# ToolChanger_RevA.net
KiCad netlist of a schematic drawn in EAGLE
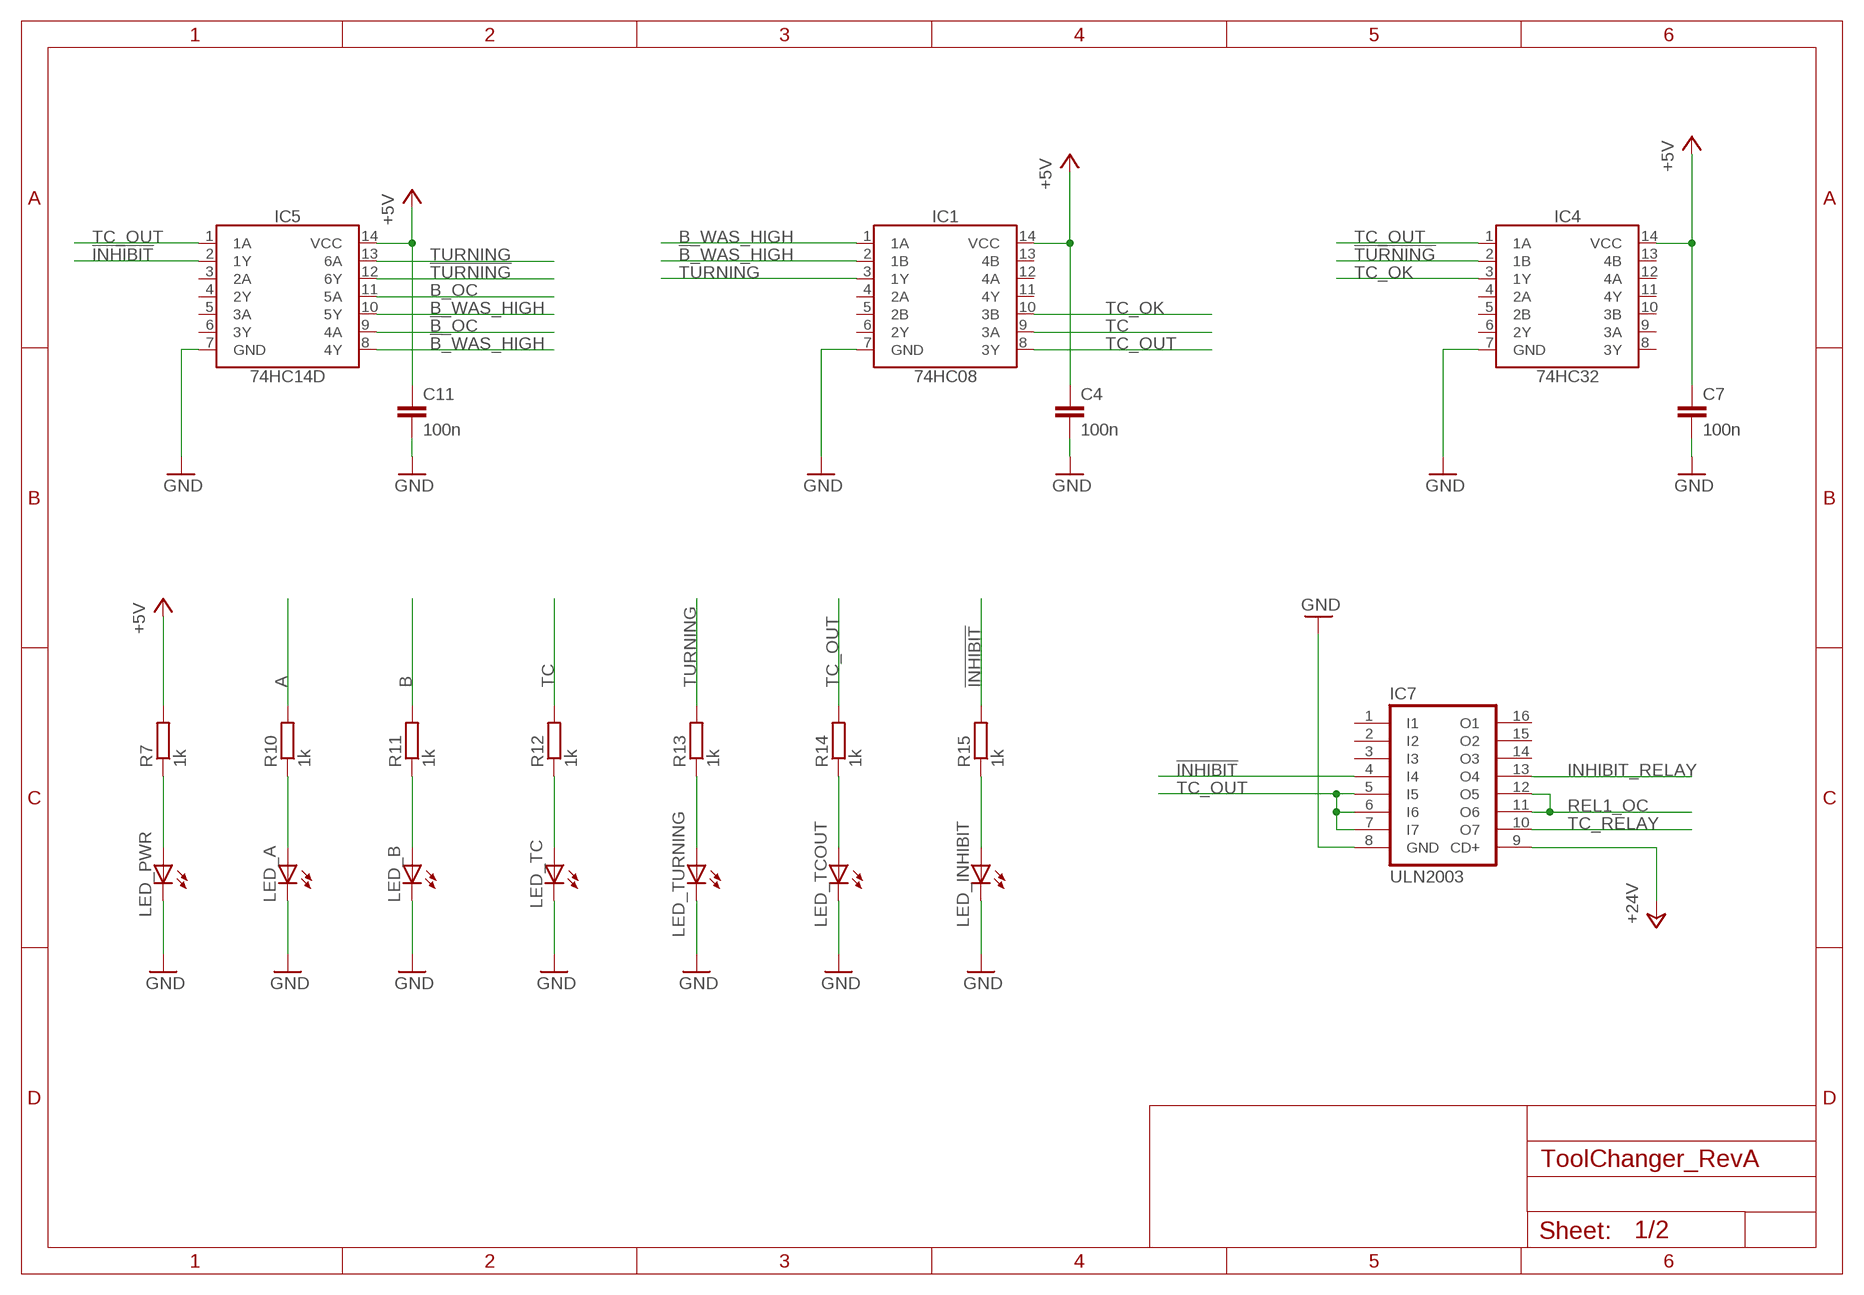
[diagram p0: schematic, sheet 1]
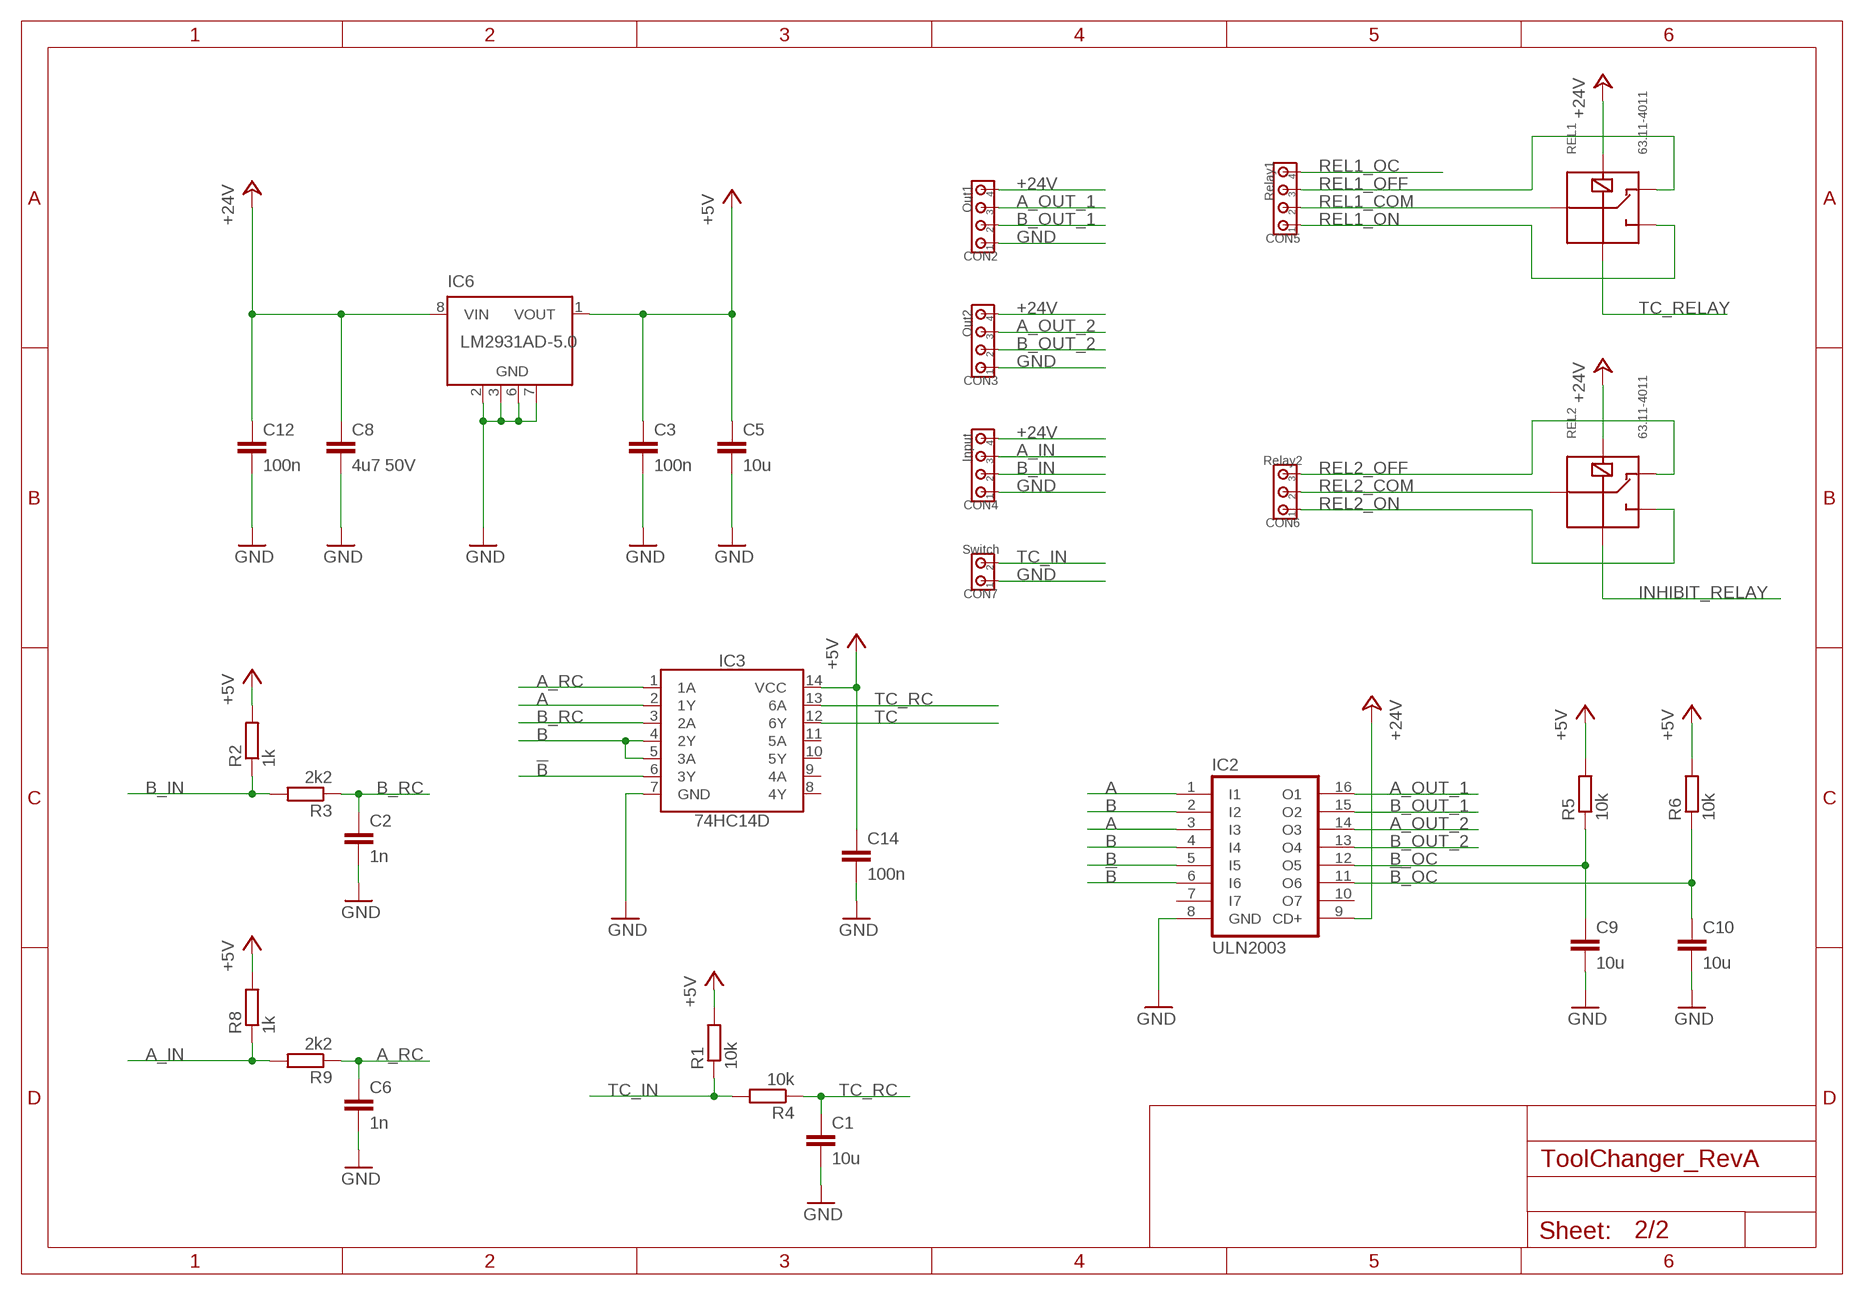
[diagram p1: schematic, sheet 2]

(export (version "E")
  (design (tool "Eeschema 10.0.6"))
  (components
    (comp (ref "C4")
      (value "100n")
      (footprint "eagle-import:C0805")
      (libsource (lib "eagle-import") (part "CC0805"))
    )
    (comp (ref "C7")
      (value "100n")
      (footprint "eagle-import:C0805")
      (libsource (lib "eagle-import") (part "CC0805"))
    )
    (comp (ref "C11")
      (value "100n")
      (footprint "eagle-import:C0805")
      (libsource (lib "eagle-import") (part "CC0805"))
    )
    (comp (ref "IC1")
      (value "74HC08")
      (footprint "eagle-import:SO14")
      (libsource (lib "eagle-import") (part "74HC08"))
    )
    (comp (ref "IC4")
      (value "74HC32")
      (footprint "eagle-import:SO14")
      (libsource (lib "eagle-import") (part "74HC32"))
    )
    (comp (ref "IC5")
      (value "74HC14D")
      (footprint "eagle-import:SO14")
      (libsource (lib "eagle-import") (part "74HC14D"))
    )
    (comp (ref "IC7")
      (value "ULN2003")
      (footprint "eagle-import:SO16")
      (libsource (lib "eagle-import") (part "ULN2003"))
    )
    (comp (ref "LED_A")
      (value "LED0805_NB")
      (footprint "eagle-import:LED0805_NOBOARDER")
      (libsource (lib "eagle-import") (part "LED0805_NB"))
    )
    (comp (ref "LED_B")
      (value "LED0805_NB")
      (footprint "eagle-import:LED0805_NOBOARDER")
      (libsource (lib "eagle-import") (part "LED0805_NB"))
    )
    (comp (ref "LED_INHIBIT")
      (value "LED0805_NB")
      (footprint "eagle-import:LED0805_NOBOARDER")
      (libsource (lib "eagle-import") (part "LED0805_NB"))
    )
    (comp (ref "LED_PWR")
      (value "LED0805_NB")
      (footprint "eagle-import:LED0805_NOBOARDER")
      (libsource (lib "eagle-import") (part "LED0805_NB"))
    )
    (comp (ref "LED_TC")
      (value "LED0805_NB")
      (footprint "eagle-import:LED0805_NOBOARDER")
      (libsource (lib "eagle-import") (part "LED0805_NB"))
    )
    (comp (ref "LED_TCOUT")
      (value "LED0805_NB")
      (footprint "eagle-import:LED0805_NOBOARDER")
      (libsource (lib "eagle-import") (part "LED0805_NB"))
    )
    (comp (ref "LED_TURNING")
      (value "LED0805_NB")
      (footprint "eagle-import:LED0805_NOBOARDER")
      (libsource (lib "eagle-import") (part "LED0805_NB"))
    )
    (comp (ref "R7")
      (value "1k")
      (footprint "eagle-import:R0805")
      (libsource (lib "eagle-import") (part "RESISTORR0805"))
    )
    (comp (ref "R10")
      (value "1k")
      (footprint "eagle-import:R0805")
      (libsource (lib "eagle-import") (part "RESISTORR0805"))
    )
    (comp (ref "R11")
      (value "1k")
      (footprint "eagle-import:R0805")
      (libsource (lib "eagle-import") (part "RESISTORR0805"))
    )
    (comp (ref "R12")
      (value "1k")
      (footprint "eagle-import:R0805")
      (libsource (lib "eagle-import") (part "RESISTORR0805"))
    )
    (comp (ref "R13")
      (value "1k")
      (footprint "eagle-import:R0805")
      (libsource (lib "eagle-import") (part "RESISTORR0805"))
    )
    (comp (ref "R14")
      (value "1k")
      (footprint "eagle-import:R0805")
      (libsource (lib "eagle-import") (part "RESISTORR0805"))
    )
    (comp (ref "R15")
      (value "1k")
      (footprint "eagle-import:R0805")
      (libsource (lib "eagle-import") (part "RESISTORR0805"))
    )
    (comp (ref "C1")
      (value "10u")
      (footprint "eagle-import:C0805")
      (libsource (lib "eagle-import") (part "CC0805"))
    )
    (comp (ref "C2")
      (value "1n")
      (footprint "eagle-import:C0805")
      (libsource (lib "eagle-import") (part "CC0805"))
    )
    (comp (ref "C3")
      (value "100n")
      (footprint "eagle-import:C0805")
      (libsource (lib "eagle-import") (part "CC0805"))
    )
    (comp (ref "C5")
      (value "10u")
      (footprint "eagle-import:C0805")
      (libsource (lib "eagle-import") (part "CC0805"))
    )
    (comp (ref "C6")
      (value "1n")
      (footprint "eagle-import:C0805")
      (libsource (lib "eagle-import") (part "CC0805"))
    )
    (comp (ref "C8")
      (value "4u7 50V")
      (footprint "eagle-import:C1206")
      (libsource (lib "eagle-import") (part "CC1206"))
    )
    (comp (ref "C9")
      (value "10u")
      (footprint "eagle-import:C0805")
      (libsource (lib "eagle-import") (part "CC0805"))
    )
    (comp (ref "C10")
      (value "10u")
      (footprint "eagle-import:C0805")
      (libsource (lib "eagle-import") (part "CC0805"))
    )
    (comp (ref "C12")
      (value "100n")
      (footprint "eagle-import:C0805")
      (libsource (lib "eagle-import") (part "CC0805"))
    )
    (comp (ref "C14")
      (value "100n")
      (footprint "eagle-import:C0805")
      (libsource (lib "eagle-import") (part "CC0805"))
    )
    (comp (ref "CON2")
      (value "Out1")
      (footprint "eagle-import:3.5MM_4X")
      (libsource (lib "eagle-import") (part "CON_4X3.5MM"))
    )
    (comp (ref "CON3")
      (value "Out2")
      (footprint "eagle-import:3.5MM_4X")
      (libsource (lib "eagle-import") (part "CON_4X3.5MM"))
    )
    (comp (ref "CON4")
      (value "Input")
      (footprint "eagle-import:3.5MM_4X")
      (libsource (lib "eagle-import") (part "CON_4X3.5MM"))
    )
    (comp (ref "CON5")
      (value "Relay1")
      (footprint "eagle-import:200MIL_4X")
      (libsource (lib "eagle-import") (part "CON_4X200MIL"))
    )
    (comp (ref "CON6")
      (value "Relay2")
      (footprint "eagle-import:200MIL_3X")
      (libsource (lib "eagle-import") (part "CON_3X200MIL"))
    )
    (comp (ref "CON7")
      (value "Switch")
      (footprint "eagle-import:3.5MM_2X")
      (libsource (lib "eagle-import") (part "CON_2X3.5MM"))
    )
    (comp (ref "IC2")
      (value "ULN2003")
      (footprint "eagle-import:SO16")
      (libsource (lib "eagle-import") (part "ULN2003"))
    )
    (comp (ref "IC3")
      (value "74HC14D")
      (footprint "eagle-import:SO14")
      (libsource (lib "eagle-import") (part "74HC14D"))
    )
    (comp (ref "IC6")
      (value "LM2931AD-5.0")
      (footprint "eagle-import:SOIC8")
      (libsource (lib "eagle-import") (part "LM2931AD-5.0"))
    )
    (comp (ref "R1")
      (value "10k")
      (footprint "eagle-import:R0805")
      (libsource (lib "eagle-import") (part "RESISTORR0805"))
    )
    (comp (ref "R2")
      (value "1k")
      (footprint "eagle-import:R0805")
      (libsource (lib "eagle-import") (part "RESISTORR0805"))
    )
    (comp (ref "R3")
      (value "2k2")
      (footprint "eagle-import:R0805")
      (libsource (lib "eagle-import") (part "RESISTORR0805"))
    )
    (comp (ref "R4")
      (value "10k")
      (footprint "eagle-import:R0805")
      (libsource (lib "eagle-import") (part "RESISTORR0805"))
    )
    (comp (ref "R5")
      (value "10k")
      (footprint "eagle-import:R0805")
      (libsource (lib "eagle-import") (part "RESISTORR0805"))
    )
    (comp (ref "R6")
      (value "10k")
      (footprint "eagle-import:R0805")
      (libsource (lib "eagle-import") (part "RESISTORR0805"))
    )
    (comp (ref "R8")
      (value "1k")
      (footprint "eagle-import:R0805")
      (libsource (lib "eagle-import") (part "RESISTORR0805"))
    )
    (comp (ref "R9")
      (value "2k2")
      (footprint "eagle-import:R0805")
      (libsource (lib "eagle-import") (part "RESISTORR0805"))
    )
    (comp (ref "REL1")
      (value "63.11-4011")
      (footprint "eagle-import:G5LE")
      (libsource (lib "eagle-import") (part "63.11-4011"))
    )
    (comp (ref "REL2")
      (value "63.11-4011")
      (footprint "eagle-import:G5LE")
      (libsource (lib "eagle-import") (part "63.11-4011"))
    )
  )
  (nets
    (net (code "1") (name "+5V") (class "Default")
      (node (ref "C11") (pin "1") (pinfunction "1_1") (pintype "passive"))
      (node (ref "C14") (pin "1") (pinfunction "1_1") (pintype "passive"))
      (node (ref "C3") (pin "1") (pinfunction "1_1") (pintype "passive"))
      (node (ref "C4") (pin "1") (pinfunction "1_1") (pintype "passive"))
      (node (ref "C5") (pin "1") (pinfunction "1_1") (pintype "passive"))
      (node (ref "C7") (pin "1") (pinfunction "1_1") (pintype "passive"))
      (node (ref "IC1") (pin "14") (pinfunction "VCC_14") (pintype "power_in"))
      (node (ref "IC3") (pin "14") (pinfunction "VCC_14") (pintype "power_in"))
      (node (ref "IC4") (pin "14") (pinfunction "VCC_14") (pintype "power_in"))
      (node (ref "IC5") (pin "14") (pinfunction "VCC_14") (pintype "power_in"))
      (node (ref "IC6") (pin "1") (pinfunction "VOUT_1") (pintype "output"))
      (node (ref "R1") (pin "2") (pinfunction "2_2") (pintype "passive"))
      (node (ref "R2") (pin "2") (pinfunction "2_2") (pintype "passive"))
      (node (ref "R5") (pin "2") (pinfunction "2_2") (pintype "passive"))
      (node (ref "R6") (pin "2") (pinfunction "2_2") (pintype "passive"))
      (node (ref "R7") (pin "2") (pinfunction "2_2") (pintype "passive"))
      (node (ref "R8") (pin "2") (pinfunction "2_2") (pintype "passive"))
    )
    (net (code "2") (name "+24V") (class "Default")
      (node (ref "C12") (pin "1") (pinfunction "1_1") (pintype "passive"))
      (node (ref "C8") (pin "1") (pinfunction "1_1") (pintype "passive"))
      (node (ref "CON2") (pin "4") (pinfunction "4_4") (pintype "passive"))
      (node (ref "CON3") (pin "4") (pinfunction "4_4") (pintype "passive"))
      (node (ref "CON4") (pin "4") (pinfunction "4_4") (pintype "passive"))
      (node (ref "IC2") (pin "9") (pinfunction "CD+_9") (pintype "passive"))
      (node (ref "IC6") (pin "8") (pinfunction "VIN_8") (pintype "passive"))
      (node (ref "IC7") (pin "9") (pinfunction "CD+_9") (pintype "passive"))
      (node (ref "REL1") (pin "2") (pinfunction "2_2") (pintype "passive"))
      (node (ref "REL2") (pin "2") (pinfunction "2_2") (pintype "passive"))
    )
    (net (code "3") (name "A") (class "Default")
      (node (ref "IC2") (pin "1") (pinfunction "I1_1") (pintype "input"))
      (node (ref "IC2") (pin "3") (pinfunction "I3_3") (pintype "input"))
      (node (ref "IC3") (pin "2") (pinfunction "1Y_2") (pintype "input"))
      (node (ref "R10") (pin "2") (pinfunction "2_2") (pintype "passive"))
    )
    (net (code "4") (name "A_IN") (class "Default")
      (node (ref "CON4") (pin "3") (pinfunction "3_3") (pintype "passive"))
      (node (ref "R8") (pin "1") (pinfunction "1_1") (pintype "passive"))
      (node (ref "R9") (pin "2") (pinfunction "2_2") (pintype "passive"))
    )
    (net (code "5") (name "A_OUT_1") (class "Default")
      (node (ref "CON2") (pin "3") (pinfunction "3_3") (pintype "passive"))
      (node (ref "IC2") (pin "16") (pinfunction "O1_16") (pintype "open_collector"))
    )
    (net (code "6") (name "A_OUT_2") (class "Default")
      (node (ref "CON3") (pin "3") (pinfunction "3_3") (pintype "passive"))
      (node (ref "IC2") (pin "14") (pinfunction "O3_14") (pintype "open_collector"))
    )
    (net (code "7") (name "A_RC") (class "Default")
      (node (ref "C6") (pin "1") (pinfunction "1_1") (pintype "passive"))
      (node (ref "IC3") (pin "1") (pinfunction "1A_1") (pintype "input"))
      (node (ref "R9") (pin "1") (pinfunction "1_1") (pintype "passive"))
    )
    (net (code "8") (name "B") (class "Default")
      (node (ref "IC2") (pin "2") (pinfunction "I2_2") (pintype "input"))
      (node (ref "IC2") (pin "4") (pinfunction "I4_4") (pintype "input"))
      (node (ref "IC2") (pin "5") (pinfunction "I5_5") (pintype "input"))
      (node (ref "IC3") (pin "4") (pinfunction "2Y_4") (pintype "input"))
      (node (ref "IC3") (pin "5") (pinfunction "3A_5") (pintype "input"))
      (node (ref "R11") (pin "2") (pinfunction "2_2") (pintype "passive"))
    )
    (net (code "9") (name "B_IN") (class "Default")
      (node (ref "CON4") (pin "2") (pinfunction "2_2") (pintype "passive"))
      (node (ref "R2") (pin "1") (pinfunction "1_1") (pintype "passive"))
      (node (ref "R3") (pin "2") (pinfunction "2_2") (pintype "passive"))
    )
    (net (code "10") (name "B_OC") (class "Default")
      (node (ref "C9") (pin "1") (pinfunction "1_1") (pintype "passive"))
      (node (ref "IC2") (pin "12") (pinfunction "O5_12") (pintype "open_collector"))
      (node (ref "IC5") (pin "11") (pinfunction "5A_11") (pintype "bidirectional"))
      (node (ref "R5") (pin "1") (pinfunction "1_1") (pintype "passive"))
    )
    (net (code "11") (name "B_OUT_1") (class "Default")
      (node (ref "CON2") (pin "2") (pinfunction "2_2") (pintype "passive"))
      (node (ref "IC2") (pin "15") (pinfunction "O2_15") (pintype "open_collector"))
    )
    (net (code "12") (name "B_OUT_2") (class "Default")
      (node (ref "CON3") (pin "2") (pinfunction "2_2") (pintype "passive"))
      (node (ref "IC2") (pin "13") (pinfunction "O4_13") (pintype "open_collector"))
    )
    (net (code "13") (name "B_RC") (class "Default")
      (node (ref "C2") (pin "1") (pinfunction "1_1") (pintype "passive"))
      (node (ref "IC3") (pin "3") (pinfunction "2A_3") (pintype "input"))
      (node (ref "R3") (pin "1") (pinfunction "1_1") (pintype "passive"))
    )
    (net (code "14") (name "B_WAS_HIGH") (class "Default")
      (node (ref "IC1") (pin "1") (pinfunction "1A_1") (pintype "input"))
      (node (ref "IC5") (pin "10") (pinfunction "5Y_10") (pintype "bidirectional"))
    )
    (net (code "15") (name "GND") (class "Default")
      (node (ref "C1") (pin "2") (pinfunction "2_2") (pintype "passive"))
      (node (ref "C10") (pin "2") (pinfunction "2_2") (pintype "passive"))
      (node (ref "C11") (pin "2") (pinfunction "2_2") (pintype "passive"))
      (node (ref "C12") (pin "2") (pinfunction "2_2") (pintype "passive"))
      (node (ref "C14") (pin "2") (pinfunction "2_2") (pintype "passive"))
      (node (ref "C2") (pin "2") (pinfunction "2_2") (pintype "passive"))
      (node (ref "C3") (pin "2") (pinfunction "2_2") (pintype "passive"))
      (node (ref "C4") (pin "2") (pinfunction "2_2") (pintype "passive"))
      (node (ref "C5") (pin "2") (pinfunction "2_2") (pintype "passive"))
      (node (ref "C6") (pin "2") (pinfunction "2_2") (pintype "passive"))
      (node (ref "C7") (pin "2") (pinfunction "2_2") (pintype "passive"))
      (node (ref "C8") (pin "2") (pinfunction "2_2") (pintype "passive"))
      (node (ref "C9") (pin "2") (pinfunction "2_2") (pintype "passive"))
      (node (ref "CON2") (pin "1") (pinfunction "1_1") (pintype "passive"))
      (node (ref "CON3") (pin "1") (pinfunction "1_1") (pintype "passive"))
      (node (ref "CON4") (pin "1") (pinfunction "1_1") (pintype "passive"))
      (node (ref "CON7") (pin "1") (pinfunction "1_1") (pintype "passive"))
      (node (ref "IC1") (pin "7") (pinfunction "GND_7") (pintype "bidirectional"))
      (node (ref "IC2") (pin "8") (pinfunction "GND_8") (pintype "power_in"))
      (node (ref "IC3") (pin "7") (pinfunction "GND_7") (pintype "bidirectional"))
      (node (ref "IC4") (pin "7") (pinfunction "GND_7") (pintype "bidirectional"))
      (node (ref "IC5") (pin "7") (pinfunction "GND_7") (pintype "bidirectional"))
      (node (ref "IC6") (pin "2") (pinfunction "GND_2") (pintype "power_in"))
      (node (ref "IC6") (pin "3") (pinfunction "GND_3") (pintype "power_in"))
      (node (ref "IC6") (pin "6") (pinfunction "GND_6") (pintype "power_in"))
      (node (ref "IC6") (pin "7") (pinfunction "GND_7") (pintype "power_in"))
      (node (ref "IC7") (pin "8") (pinfunction "GND_8") (pintype "power_in"))
      (node (ref "LED_A") (pin "C") (pinfunction "C_C") (pintype "passive"))
      (node (ref "LED_B") (pin "C") (pinfunction "C_C") (pintype "passive"))
      (node (ref "LED_INHIBIT") (pin "C") (pinfunction "C_C") (pintype "passive"))
      (node (ref "LED_PWR") (pin "C") (pinfunction "C_C") (pintype "passive"))
      (node (ref "LED_TC") (pin "C") (pinfunction "C_C") (pintype "passive"))
      (node (ref "LED_TCOUT") (pin "C") (pinfunction "C_C") (pintype "passive"))
      (node (ref "LED_TURNING") (pin "C") (pinfunction "C_C") (pintype "passive"))
    )
    (net (code "16") (name "INHIBIT_RELAY") (class "Default")
      (node (ref "IC7") (pin "13") (pinfunction "O4_13") (pintype "open_collector"))
      (node (ref "REL2") (pin "1") (pinfunction "1_1") (pintype "passive"))
    )
    (net (code "17") (name "Net-(LED_A-PadA)") (class "Default")
      (node (ref "LED_A") (pin "A") (pinfunction "A_A") (pintype "passive"))
      (node (ref "R10") (pin "1") (pinfunction "1_1") (pintype "passive"))
    )
    (net (code "18") (name "Net-(LED_B-PadA)") (class "Default")
      (node (ref "LED_B") (pin "A") (pinfunction "A_A") (pintype "passive"))
      (node (ref "R11") (pin "1") (pinfunction "1_1") (pintype "passive"))
    )
    (net (code "19") (name "Net-(LED_INHIBIT-PadA)") (class "Default")
      (node (ref "LED_INHIBIT") (pin "A") (pinfunction "A_A") (pintype "passive"))
      (node (ref "R15") (pin "1") (pinfunction "1_1") (pintype "passive"))
    )
    (net (code "20") (name "Net-(LED_PWR-PadA)") (class "Default")
      (node (ref "LED_PWR") (pin "A") (pinfunction "A_A") (pintype "passive"))
      (node (ref "R7") (pin "1") (pinfunction "1_1") (pintype "passive"))
    )
    (net (code "21") (name "Net-(LED_TC-PadA)") (class "Default")
      (node (ref "LED_TC") (pin "A") (pinfunction "A_A") (pintype "passive"))
      (node (ref "R12") (pin "1") (pinfunction "1_1") (pintype "passive"))
    )
    (net (code "22") (name "Net-(LED_TCOUT-PadA)") (class "Default")
      (node (ref "LED_TCOUT") (pin "A") (pinfunction "A_A") (pintype "passive"))
      (node (ref "R14") (pin "1") (pinfunction "1_1") (pintype "passive"))
    )
    (net (code "23") (name "Net-(LED_TURNING-PadA)") (class "Default")
      (node (ref "LED_TURNING") (pin "A") (pinfunction "A_A") (pintype "passive"))
      (node (ref "R13") (pin "1") (pinfunction "1_1") (pintype "passive"))
    )
    (net (code "24") (name "REL1_COM") (class "Default")
      (node (ref "CON5") (pin "2") (pinfunction "2_2") (pintype "passive"))
      (node (ref "REL1") (pin "COM") (pinfunction "COM_COM") (pintype "passive"))
    )
    (net (code "25") (name "REL1_OC") (class "Default")
      (node (ref "CON5") (pin "4") (pinfunction "4_4") (pintype "passive"))
      (node (ref "IC7") (pin "11") (pinfunction "O6_11") (pintype "open_collector"))
      (node (ref "IC7") (pin "12") (pinfunction "O5_12") (pintype "open_collector"))
    )
    (net (code "26") (name "REL1_OFF") (class "Default")
      (node (ref "CON5") (pin "3") (pinfunction "3_3") (pintype "passive"))
      (node (ref "REL1") (pin "O") (pinfunction "O_O") (pintype "passive"))
    )
    (net (code "27") (name "REL1_ON") (class "Default")
      (node (ref "CON5") (pin "1") (pinfunction "1_1") (pintype "passive"))
      (node (ref "REL1") (pin "C") (pinfunction "C_C") (pintype "passive"))
    )
    (net (code "28") (name "REL2_COM") (class "Default")
      (node (ref "CON6") (pin "2") (pinfunction "2_2") (pintype "passive"))
      (node (ref "REL2") (pin "COM") (pinfunction "COM_COM") (pintype "passive"))
    )
    (net (code "29") (name "REL2_OFF") (class "Default")
      (node (ref "CON6") (pin "3") (pinfunction "3_3") (pintype "passive"))
      (node (ref "REL2") (pin "O") (pinfunction "O_O") (pintype "passive"))
    )
    (net (code "30") (name "REL2_ON") (class "Default")
      (node (ref "CON6") (pin "1") (pinfunction "1_1") (pintype "passive"))
      (node (ref "REL2") (pin "C") (pinfunction "C_C") (pintype "passive"))
    )
    (net (code "31") (name "TC") (class "Default")
      (node (ref "IC1") (pin "9") (pinfunction "3A_9") (pintype "bidirectional"))
      (node (ref "IC3") (pin "12") (pinfunction "6Y_12") (pintype "bidirectional"))
      (node (ref "R12") (pin "2") (pinfunction "2_2") (pintype "passive"))
    )
    (net (code "32") (name "TC_IN") (class "Default")
      (node (ref "CON7") (pin "2") (pinfunction "2_2") (pintype "passive"))
      (node (ref "R1") (pin "1") (pinfunction "1_1") (pintype "passive"))
      (node (ref "R4") (pin "2") (pinfunction "2_2") (pintype "passive"))
    )
    (net (code "33") (name "TC_OK") (class "Default")
      (node (ref "IC1") (pin "10") (pinfunction "3B_10") (pintype "bidirectional"))
      (node (ref "IC4") (pin "3") (pinfunction "1Y_3") (pintype "input"))
    )
    (net (code "34") (name "TC_OUT") (class "Default")
      (node (ref "IC1") (pin "8") (pinfunction "3Y_8") (pintype "bidirectional"))
      (node (ref "IC4") (pin "1") (pinfunction "1A_1") (pintype "input"))
      (node (ref "IC5") (pin "1") (pinfunction "1A_1") (pintype "input"))
      (node (ref "IC7") (pin "5") (pinfunction "I5_5") (pintype "input"))
      (node (ref "IC7") (pin "6") (pinfunction "I6_6") (pintype "input"))
      (node (ref "IC7") (pin "7") (pinfunction "I7_7") (pintype "input"))
      (node (ref "R14") (pin "2") (pinfunction "2_2") (pintype "passive"))
    )
    (net (code "35") (name "TC_RC") (class "Default")
      (node (ref "C1") (pin "1") (pinfunction "1_1") (pintype "passive"))
      (node (ref "IC3") (pin "13") (pinfunction "6A_13") (pintype "bidirectional"))
      (node (ref "R4") (pin "1") (pinfunction "1_1") (pintype "passive"))
    )
    (net (code "36") (name "TC_RELAY") (class "Default")
      (node (ref "IC7") (pin "10") (pinfunction "O7_10") (pintype "open_collector"))
      (node (ref "REL1") (pin "1") (pinfunction "1_1") (pintype "passive"))
    )
    (net (code "37") (name "TURNING") (class "Default")
      (node (ref "IC1") (pin "3") (pinfunction "1Y_3") (pintype "input"))
      (node (ref "IC5") (pin "13") (pinfunction "6A_13") (pintype "bidirectional"))
      (node (ref "R13") (pin "2") (pinfunction "2_2") (pintype "passive"))
    )
    (net (code "38") (name "unconnected-(IC1-2A-Pad4)") (class "Default")
      (node (ref "IC1") (pin "4") (pinfunction "2A_4") (pintype "input"))
    )
    (net (code "39") (name "unconnected-(IC1-2B-Pad5)") (class "Default")
      (node (ref "IC1") (pin "5") (pinfunction "2B_5") (pintype "input"))
    )
    (net (code "40") (name "unconnected-(IC1-2Y-Pad6)") (class "Default")
      (node (ref "IC1") (pin "6") (pinfunction "2Y_6") (pintype "input"))
    )
    (net (code "41") (name "unconnected-(IC1-4A-Pad12)") (class "Default")
      (node (ref "IC1") (pin "12") (pinfunction "4A_12") (pintype "bidirectional"))
    )
    (net (code "42") (name "unconnected-(IC1-4B-Pad13)") (class "Default")
      (node (ref "IC1") (pin "13") (pinfunction "4B_13") (pintype "bidirectional"))
    )
    (net (code "43") (name "unconnected-(IC1-4Y-Pad11)") (class "Default")
      (node (ref "IC1") (pin "11") (pinfunction "4Y_11") (pintype "bidirectional"))
    )
    (net (code "44") (name "unconnected-(IC2-I7-Pad7)") (class "Default")
      (node (ref "IC2") (pin "7") (pinfunction "I7_7") (pintype "input"))
    )
    (net (code "45") (name "unconnected-(IC2-O7-Pad10)") (class "Default")
      (node (ref "IC2") (pin "10") (pinfunction "O7_10") (pintype "open_collector"))
    )
    (net (code "46") (name "unconnected-(IC3-4A-Pad9)") (class "Default")
      (node (ref "IC3") (pin "9") (pinfunction "4A_9") (pintype "bidirectional"))
    )
    (net (code "47") (name "unconnected-(IC3-4Y-Pad8)") (class "Default")
      (node (ref "IC3") (pin "8") (pinfunction "4Y_8") (pintype "bidirectional"))
    )
    (net (code "48") (name "unconnected-(IC3-5A-Pad11)") (class "Default")
      (node (ref "IC3") (pin "11") (pinfunction "5A_11") (pintype "bidirectional"))
    )
    (net (code "49") (name "unconnected-(IC3-5Y-Pad10)") (class "Default")
      (node (ref "IC3") (pin "10") (pinfunction "5Y_10") (pintype "bidirectional"))
    )
    (net (code "50") (name "unconnected-(IC4-2A-Pad4)") (class "Default")
      (node (ref "IC4") (pin "4") (pinfunction "2A_4") (pintype "input"))
    )
    (net (code "51") (name "unconnected-(IC4-2B-Pad5)") (class "Default")
      (node (ref "IC4") (pin "5") (pinfunction "2B_5") (pintype "input"))
    )
    (net (code "52") (name "unconnected-(IC4-2Y-Pad6)") (class "Default")
      (node (ref "IC4") (pin "6") (pinfunction "2Y_6") (pintype "input"))
    )
    (net (code "53") (name "unconnected-(IC4-3A-Pad9)") (class "Default")
      (node (ref "IC4") (pin "9") (pinfunction "3A_9") (pintype "bidirectional"))
    )
    (net (code "54") (name "unconnected-(IC4-3B-Pad10)") (class "Default")
      (node (ref "IC4") (pin "10") (pinfunction "3B_10") (pintype "bidirectional"))
    )
    (net (code "55") (name "unconnected-(IC4-3Y-Pad8)") (class "Default")
      (node (ref "IC4") (pin "8") (pinfunction "3Y_8") (pintype "bidirectional"))
    )
    (net (code "56") (name "unconnected-(IC4-4A-Pad12)") (class "Default")
      (node (ref "IC4") (pin "12") (pinfunction "4A_12") (pintype "bidirectional"))
    )
    (net (code "57") (name "unconnected-(IC4-4B-Pad13)") (class "Default")
      (node (ref "IC4") (pin "13") (pinfunction "4B_13") (pintype "bidirectional"))
    )
    (net (code "58") (name "unconnected-(IC4-4Y-Pad11)") (class "Default")
      (node (ref "IC4") (pin "11") (pinfunction "4Y_11") (pintype "bidirectional"))
    )
    (net (code "59") (name "unconnected-(IC5-2A-Pad3)") (class "Default")
      (node (ref "IC5") (pin "3") (pinfunction "2A_3") (pintype "input"))
    )
    (net (code "60") (name "unconnected-(IC5-2Y-Pad4)") (class "Default")
      (node (ref "IC5") (pin "4") (pinfunction "2Y_4") (pintype "input"))
    )
    (net (code "61") (name "unconnected-(IC5-3A-Pad5)") (class "Default")
      (node (ref "IC5") (pin "5") (pinfunction "3A_5") (pintype "input"))
    )
    (net (code "62") (name "unconnected-(IC5-3Y-Pad6)") (class "Default")
      (node (ref "IC5") (pin "6") (pinfunction "3Y_6") (pintype "input"))
    )
    (net (code "63") (name "unconnected-(IC7-I1-Pad1)") (class "Default")
      (node (ref "IC7") (pin "1") (pinfunction "I1_1") (pintype "input"))
    )
    (net (code "64") (name "unconnected-(IC7-I2-Pad2)") (class "Default")
      (node (ref "IC7") (pin "2") (pinfunction "I2_2") (pintype "input"))
    )
    (net (code "65") (name "unconnected-(IC7-I3-Pad3)") (class "Default")
      (node (ref "IC7") (pin "3") (pinfunction "I3_3") (pintype "input"))
    )
    (net (code "66") (name "unconnected-(IC7-O1-Pad16)") (class "Default")
      (node (ref "IC7") (pin "16") (pinfunction "O1_16") (pintype "open_collector"))
    )
    (net (code "67") (name "unconnected-(IC7-O2-Pad15)") (class "Default")
      (node (ref "IC7") (pin "15") (pinfunction "O2_15") (pintype "open_collector"))
    )
    (net (code "68") (name "unconnected-(IC7-O3-Pad14)") (class "Default")
      (node (ref "IC7") (pin "14") (pinfunction "O3_14") (pintype "open_collector"))
    )
    (net (code "69") (name "~{B}") (class "Default")
      (node (ref "IC2") (pin "6") (pinfunction "I6_6") (pintype "input"))
      (node (ref "IC3") (pin "6") (pinfunction "3Y_6") (pintype "input"))
    )
    (net (code "70") (name "~{B}_OC") (class "Default")
      (node (ref "C10") (pin "1") (pinfunction "1_1") (pintype "passive"))
      (node (ref "IC2") (pin "11") (pinfunction "O6_11") (pintype "open_collector"))
      (node (ref "IC5") (pin "9") (pinfunction "4A_9") (pintype "bidirectional"))
      (node (ref "R6") (pin "1") (pinfunction "1_1") (pintype "passive"))
    )
    (net (code "71") (name "~{B}_WAS_HIGH") (class "Default")
      (node (ref "IC1") (pin "2") (pinfunction "1B_2") (pintype "input"))
      (node (ref "IC5") (pin "8") (pinfunction "4Y_8") (pintype "bidirectional"))
    )
    (net (code "72") (name "~{INHIBIT}") (class "Default")
      (node (ref "IC5") (pin "2") (pinfunction "1Y_2") (pintype "input"))
      (node (ref "IC7") (pin "4") (pinfunction "I4_4") (pintype "input"))
      (node (ref "R15") (pin "2") (pinfunction "2_2") (pintype "passive"))
    )
    (net (code "73") (name "~{TURNING}") (class "Default")
      (node (ref "IC4") (pin "2") (pinfunction "1B_2") (pintype "input"))
      (node (ref "IC5") (pin "12") (pinfunction "6Y_12") (pintype "bidirectional"))
    )
  )
)
